# atmega16u2custom2.net
KiCad netlist of a schematic drawn in EAGLE
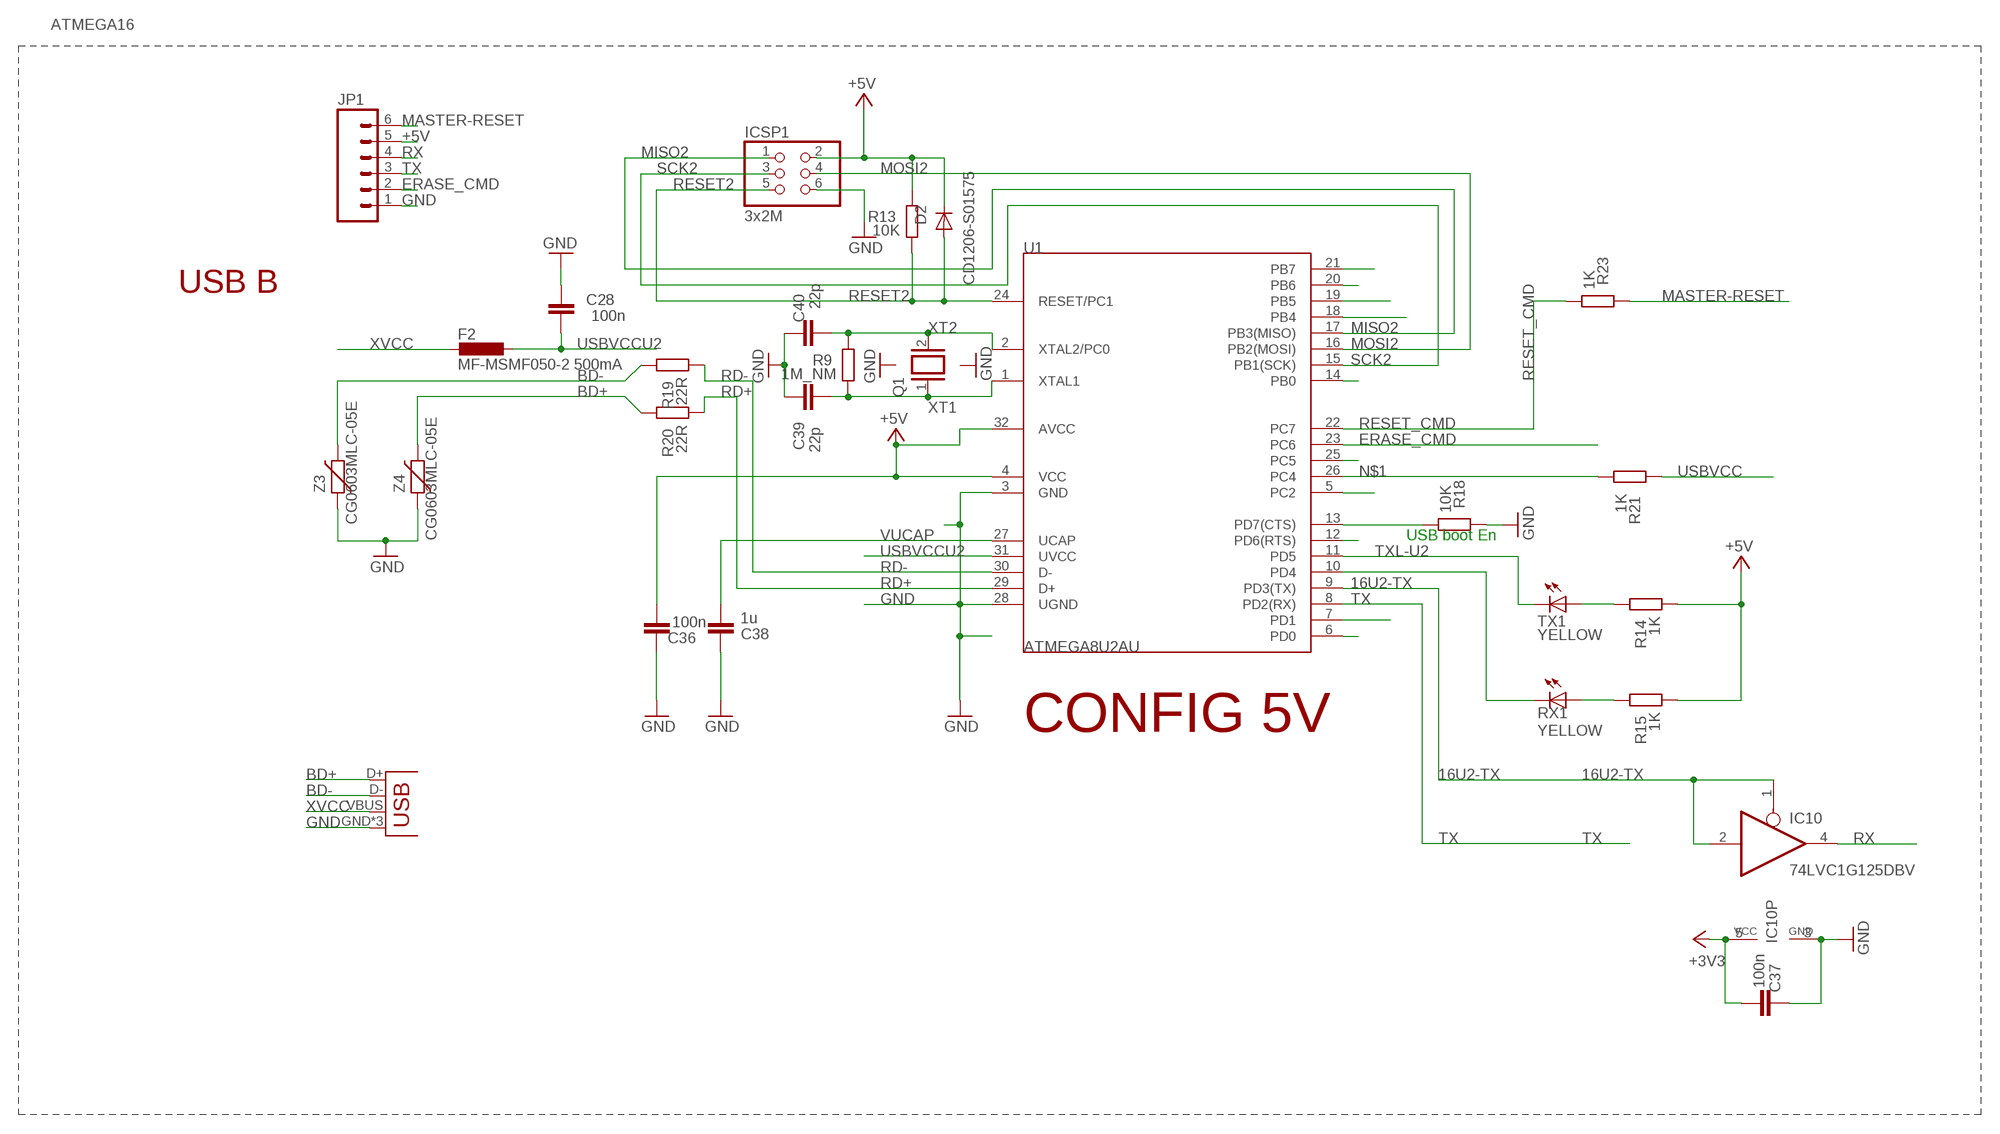
[diagram p0: schematic, sheet 1]

(export (version "E")
  (design (tool "Eeschema 10.0.6"))
  (components
    (comp (ref "C28")
      (value "100n")
      (footprint "eagle-import:C0805")
      (libsource (lib "eagle-import") (part "C-EUC0805"))
    )
    (comp (ref "C36")
      (value "100n")
      (footprint "eagle-import:C0805")
      (libsource (lib "eagle-import") (part "C-EUC0805"))
    )
    (comp (ref "C37")
      (value "100n")
      (footprint "eagle-import:C0805")
      (libsource (lib "eagle-import") (part "C-EUC0805"))
    )
    (comp (ref "C38")
      (value "1u")
      (footprint "eagle-import:C0805")
      (libsource (lib "eagle-import") (part "C-EUC0805"))
    )
    (comp (ref "C39")
      (value "22p")
      (footprint "eagle-import:C0805")
      (libsource (lib "eagle-import") (part "C-EUC0805"))
    )
    (comp (ref "C40")
      (value "22p")
      (footprint "eagle-import:C0805")
      (libsource (lib "eagle-import") (part "C-EUC0805"))
    )
    (comp (ref "D2")
      (value "CD1206-S01575")
      (footprint "eagle-import:MINIMELF")
      (libsource (lib "eagle-import") (part "DIODE-MINIMELF"))
    )
    (comp (ref "F2")
      (value "MF-MSMF050-2 500mA")
      (footprint "eagle-import:L1812")
      (libsource (lib "eagle-import") (part "L-EUL1812"))
    )
    (comp (ref "IC10")
      (value "74LVC1G125DBV")
      (footprint "eagle-import:SOT23-5")
      (libsource (lib "eagle-import") (part "741G125DBVLVC"))
    )
    (comp (ref "ICSP1")
      (value "3x2M")
      (footprint "eagle-import:2X03")
      (libsource (lib "eagle-import") (part "PINHD-2X3"))
    )
    (comp (ref "JP1")
      (value "M06NO_SILK")
      (footprint "eagle-import:1X06_NO_SILK")
      (libsource (lib "eagle-import") (part "M06NO_SILK"))
    )
    (comp (ref "JP2")
      (value "USB-MICROB")
      (footprint "eagle-import:USB-MICROB")
      (libsource (lib "eagle-import") (part "USB-MICROB"))
    )
    (comp (ref "Q1")
      (value "XTAL/S")
      (footprint "eagle-import:QS")
      (libsource (lib "eagle-import") (part "XTAL/S"))
    )
    (comp (ref "R9")
      (value "1M_NM")
      (footprint "eagle-import:R0805")
      (libsource (lib "eagle-import") (part "R-EU_R0805"))
    )
    (comp (ref "R13")
      (value "10K")
      (footprint "eagle-import:R0805")
      (libsource (lib "eagle-import") (part "R-EU_R0805"))
    )
    (comp (ref "R14")
      (value "1K")
      (footprint "eagle-import:R0805")
      (libsource (lib "eagle-import") (part "R-EU_R0805"))
    )
    (comp (ref "R15")
      (value "1K")
      (footprint "eagle-import:R0805")
      (libsource (lib "eagle-import") (part "R-EU_R0805"))
    )
    (comp (ref "R18")
      (value "10K")
      (footprint "eagle-import:R0805")
      (libsource (lib "eagle-import") (part "R-EU_R0805"))
    )
    (comp (ref "R19")
      (value "22R")
      (footprint "eagle-import:R0805")
      (libsource (lib "eagle-import") (part "R-EU_R0805"))
    )
    (comp (ref "R20")
      (value "22R")
      (footprint "eagle-import:R0805")
      (libsource (lib "eagle-import") (part "R-EU_R0805"))
    )
    (comp (ref "R21")
      (value "1K")
      (footprint "eagle-import:R0805")
      (libsource (lib "eagle-import") (part "R-EU_R0805"))
    )
    (comp (ref "R23")
      (value "1K")
      (footprint "eagle-import:R0805")
      (libsource (lib "eagle-import") (part "R-EU_R0805"))
    )
    (comp (ref "RX1")
      (value "YELLOW")
      (footprint "eagle-import:CHIP-LED0805")
      (libsource (lib "eagle-import") (part "LEDCHIP-LED0805"))
    )
    (comp (ref "TX1")
      (value "YELLOW")
      (footprint "eagle-import:CHIP-LED0805")
      (libsource (lib "eagle-import") (part "LEDCHIP-LED0805"))
    )
    (comp (ref "U1")
      (value "ATMEGA8U2AU")
      (footprint "eagle-import:TQFP32-08")
      (libsource (lib "eagle-import") (part "ATMEGA8U2AU"))
    )
    (comp (ref "Z3")
      (value "CG0603MLC-05E")
      (footprint "eagle-import:CT_CN0603")
      (libsource (lib "eagle-import") (part "VARISTORCN0603"))
    )
    (comp (ref "Z4")
      (value "CG0603MLC-05E")
      (footprint "eagle-import:CT_CN0603")
      (libsource (lib "eagle-import") (part "VARISTORCN0603"))
    )
  )
  (nets
    (net (code "1") (name "+3V3") (class "Default")
      (node (ref "C37") (pin "1") (pinfunction "1_1") (pintype "passive"))
      (node (ref "IC10") (pin "5") (pinfunction "VCC_5") (pintype "power_in"))
    )
    (net (code "2") (name "+5V") (class "Default")
      (node (ref "C36") (pin "1") (pinfunction "1_1") (pintype "passive"))
      (node (ref "D2") (pin "C") (pinfunction "C_C") (pintype "passive"))
      (node (ref "ICSP1") (pin "2") (pinfunction "2_2") (pintype "passive"))
      (node (ref "JP1") (pin "5") (pinfunction "5_5") (pintype "passive"))
      (node (ref "R13") (pin "2") (pinfunction "2_2") (pintype "passive"))
      (node (ref "R14") (pin "1") (pinfunction "1_1") (pintype "passive"))
      (node (ref "R15") (pin "1") (pinfunction "1_1") (pintype "passive"))
      (node (ref "U1") (pin "32") (pinfunction "AVCC_32") (pintype "bidirectional"))
      (node (ref "U1") (pin "4") (pinfunction "VCC_4") (pintype "bidirectional"))
    )
    (net (code "3") (name "/16U2-TX") (class "Default")
      (node (ref "IC10") (pin "1") (pinfunction "OE_1") (pintype "input"))
      (node (ref "IC10") (pin "2") (pinfunction "I_2") (pintype "input"))
      (node (ref "U1") (pin "9") (pinfunction "PD3(TX)_9") (pintype "bidirectional"))
    )
    (net (code "4") (name "/BD+") (class "Default")
      (node (ref "JP2") (pin "D+") (pinfunction "D+_D+") (pintype "bidirectional"))
      (node (ref "R20") (pin "2") (pinfunction "2_2") (pintype "passive"))
      (node (ref "Z4") (pin "2") (pinfunction "2_2") (pintype "passive"))
    )
    (net (code "5") (name "/BD-") (class "Default")
      (node (ref "JP2") (pin "D-") (pinfunction "D-_D-") (pintype "bidirectional"))
      (node (ref "R19") (pin "2") (pinfunction "2_2") (pintype "passive"))
      (node (ref "Z3") (pin "2") (pinfunction "2_2") (pintype "passive"))
    )
    (net (code "6") (name "/ERASE_CMD") (class "Default")
      (node (ref "JP1") (pin "2") (pinfunction "2_2") (pintype "passive"))
      (node (ref "U1") (pin "23") (pinfunction "PC6_23") (pintype "bidirectional"))
    )
    (net (code "7") (name "/MASTER-RESET") (class "Default")
      (node (ref "JP1") (pin "6") (pinfunction "6_6") (pintype "passive"))
      (node (ref "R23") (pin "2") (pinfunction "2_2") (pintype "passive"))
    )
    (net (code "8") (name "/MISO2") (class "Default")
      (node (ref "ICSP1") (pin "1") (pinfunction "1_1") (pintype "passive"))
      (node (ref "U1") (pin "17") (pinfunction "PB3(MISO)_17") (pintype "bidirectional"))
    )
    (net (code "9") (name "/MOSI2") (class "Default")
      (node (ref "ICSP1") (pin "4") (pinfunction "4_4") (pintype "passive"))
      (node (ref "U1") (pin "16") (pinfunction "PB2(MOSI)_16") (pintype "bidirectional"))
    )
    (net (code "10") (name "/N$1") (class "Default")
      (node (ref "R21") (pin "1") (pinfunction "1_1") (pintype "passive"))
      (node (ref "U1") (pin "26") (pinfunction "PC4_26") (pintype "bidirectional"))
    )
    (net (code "11") (name "/RD+") (class "Default")
      (node (ref "R20") (pin "1") (pinfunction "1_1") (pintype "passive"))
      (node (ref "U1") (pin "29") (pinfunction "D+_29") (pintype "bidirectional"))
    )
    (net (code "12") (name "/RD-") (class "Default")
      (node (ref "R19") (pin "1") (pinfunction "1_1") (pintype "passive"))
      (node (ref "U1") (pin "30") (pinfunction "D-_30") (pintype "bidirectional"))
    )
    (net (code "13") (name "/RESET2") (class "Default")
      (node (ref "D2") (pin "A") (pinfunction "A_A") (pintype "passive"))
      (node (ref "ICSP1") (pin "5") (pinfunction "5_5") (pintype "passive"))
      (node (ref "R13") (pin "1") (pinfunction "1_1") (pintype "passive"))
      (node (ref "U1") (pin "24") (pinfunction "RESET/PC1_24") (pintype "bidirectional"))
    )
    (net (code "14") (name "/RESET_CMD") (class "Default")
      (node (ref "R23") (pin "1") (pinfunction "1_1") (pintype "passive"))
      (node (ref "U1") (pin "22") (pinfunction "PC7_22") (pintype "bidirectional"))
    )
    (net (code "15") (name "/RX") (class "Default")
      (node (ref "IC10") (pin "4") (pinfunction "O_4") (pintype "tri_state"))
      (node (ref "JP1") (pin "4") (pinfunction "4_4") (pintype "passive"))
    )
    (net (code "16") (name "/SCK2") (class "Default")
      (node (ref "ICSP1") (pin "3") (pinfunction "3_3") (pintype "passive"))
      (node (ref "U1") (pin "15") (pinfunction "PB1(SCK)_15") (pintype "bidirectional"))
    )
    (net (code "17") (name "/TX") (class "Default")
      (node (ref "JP1") (pin "3") (pinfunction "3_3") (pintype "passive"))
      (node (ref "U1") (pin "8") (pinfunction "PD2(RX)_8") (pintype "bidirectional"))
    )
    (net (code "18") (name "/TXL-U2") (class "Default")
      (node (ref "TX1") (pin "C") (pinfunction "C_C") (pintype "passive"))
      (node (ref "U1") (pin "11") (pinfunction "PD5_11") (pintype "bidirectional"))
    )
    (net (code "19") (name "/USBVCC") (class "Default")
      (node (ref "R21") (pin "2") (pinfunction "2_2") (pintype "passive"))
    )
    (net (code "20") (name "/USBVCCU2") (class "Default")
      (node (ref "C28") (pin "1") (pinfunction "1_1") (pintype "passive"))
      (node (ref "F2") (pin "1") (pinfunction "1_1") (pintype "passive"))
      (node (ref "U1") (pin "31") (pinfunction "UVCC_31") (pintype "bidirectional"))
    )
    (net (code "21") (name "/VUCAP") (class "Default")
      (node (ref "C38") (pin "1") (pinfunction "1_1") (pintype "passive"))
      (node (ref "U1") (pin "27") (pinfunction "UCAP_27") (pintype "bidirectional"))
    )
    (net (code "22") (name "/XT1") (class "Default")
      (node (ref "C39") (pin "1") (pinfunction "1_1") (pintype "passive"))
      (node (ref "Q1") (pin "1") (pinfunction "1_1") (pintype "passive"))
      (node (ref "R9") (pin "1") (pinfunction "1_1") (pintype "passive"))
      (node (ref "U1") (pin "1") (pinfunction "XTAL1_1") (pintype "bidirectional"))
    )
    (net (code "23") (name "/XT2") (class "Default")
      (node (ref "C40") (pin "1") (pinfunction "1_1") (pintype "passive"))
      (node (ref "Q1") (pin "2") (pinfunction "2_2") (pintype "passive"))
      (node (ref "R9") (pin "2") (pinfunction "2_2") (pintype "passive"))
      (node (ref "U1") (pin "2") (pinfunction "XTAL2/PC0_2") (pintype "bidirectional"))
    )
    (net (code "24") (name "/XVCC") (class "Default")
      (node (ref "F2") (pin "2") (pinfunction "2_2") (pintype "passive"))
      (node (ref "JP2") (pin "VBUS") (pinfunction "VBUS_VBUS") (pintype "bidirectional"))
    )
    (net (code "25") (name "GND") (class "Default")
      (node (ref "C28") (pin "2") (pinfunction "2_2") (pintype "passive"))
      (node (ref "C36") (pin "2") (pinfunction "2_2") (pintype "passive"))
      (node (ref "C37") (pin "2") (pinfunction "2_2") (pintype "passive"))
      (node (ref "C38") (pin "2") (pinfunction "2_2") (pintype "passive"))
      (node (ref "C39") (pin "2") (pinfunction "2_2") (pintype "passive"))
      (node (ref "C40") (pin "2") (pinfunction "2_2") (pintype "passive"))
      (node (ref "IC10") (pin "3") (pinfunction "GND_3") (pintype "power_in"))
      (node (ref "ICSP1") (pin "6") (pinfunction "6_6") (pintype "passive"))
      (node (ref "JP1") (pin "1") (pinfunction "1_1") (pintype "passive"))
      (node (ref "JP2") (pin "GND") (pinfunction "GND_GND") (pintype "bidirectional"))
      (node (ref "JP2") (pin "MT1") (pinfunction "GND_MT1") (pintype "bidirectional"))
      (node (ref "JP2") (pin "MT2") (pinfunction "GND_MT2") (pintype "bidirectional"))
      (node (ref "R18") (pin "2") (pinfunction "2_2") (pintype "passive"))
      (node (ref "U1") (pin "28") (pinfunction "UGND_28") (pintype "bidirectional"))
      (node (ref "U1") (pin "3") (pinfunction "GND_3") (pintype "bidirectional"))
      (node (ref "Z3") (pin "1") (pinfunction "1_1") (pintype "passive"))
      (node (ref "Z4") (pin "1") (pinfunction "1_1") (pintype "passive"))
    )
    (net (code "26") (name "Net-(R14-Pad2)") (class "Default")
      (node (ref "R14") (pin "2") (pinfunction "2_2") (pintype "passive"))
      (node (ref "TX1") (pin "A") (pinfunction "A_A") (pintype "passive"))
    )
    (net (code "27") (name "Net-(R15-Pad2)") (class "Default")
      (node (ref "R15") (pin "2") (pinfunction "2_2") (pintype "passive"))
      (node (ref "RX1") (pin "A") (pinfunction "A_A") (pintype "passive"))
    )
    (net (code "28") (name "Net-(U1-PD4)") (class "Default")
      (node (ref "RX1") (pin "C") (pinfunction "C_C") (pintype "passive"))
      (node (ref "U1") (pin "10") (pinfunction "PD4_10") (pintype "bidirectional"))
    )
    (net (code "29") (name "Net-(U1-PD7(CTS))") (class "Default")
      (node (ref "R18") (pin "1") (pinfunction "1_1") (pintype "passive"))
      (node (ref "U1") (pin "13") (pinfunction "PD7(CTS)_13") (pintype "bidirectional"))
    )
    (net (code "30") (name "unconnected-(U1-PB0-Pad14)") (class "Default")
      (node (ref "U1") (pin "14") (pinfunction "PB0_14") (pintype "bidirectional"))
    )
    (net (code "31") (name "unconnected-(U1-PB4-Pad18)") (class "Default")
      (node (ref "U1") (pin "18") (pinfunction "PB4_18") (pintype "bidirectional"))
    )
    (net (code "32") (name "unconnected-(U1-PB5-Pad19)") (class "Default")
      (node (ref "U1") (pin "19") (pinfunction "PB5_19") (pintype "bidirectional"))
    )
    (net (code "33") (name "unconnected-(U1-PB6-Pad20)") (class "Default")
      (node (ref "U1") (pin "20") (pinfunction "PB6_20") (pintype "bidirectional"))
    )
    (net (code "34") (name "unconnected-(U1-PB7-Pad21)") (class "Default")
      (node (ref "U1") (pin "21") (pinfunction "PB7_21") (pintype "bidirectional"))
    )
    (net (code "35") (name "unconnected-(U1-PC2-Pad5)") (class "Default")
      (node (ref "U1") (pin "5") (pinfunction "PC2_5") (pintype "bidirectional"))
    )
    (net (code "36") (name "unconnected-(U1-PC5-Pad25)") (class "Default")
      (node (ref "U1") (pin "25") (pinfunction "PC5_25") (pintype "bidirectional"))
    )
    (net (code "37") (name "unconnected-(U1-PD0-Pad6)") (class "Default")
      (node (ref "U1") (pin "6") (pinfunction "PD0_6") (pintype "bidirectional"))
    )
    (net (code "38") (name "unconnected-(U1-PD1-Pad7)") (class "Default")
      (node (ref "U1") (pin "7") (pinfunction "PD1_7") (pintype "bidirectional"))
    )
    (net (code "39") (name "unconnected-(U1-PD6(RTS)-Pad12)") (class "Default")
      (node (ref "U1") (pin "12") (pinfunction "PD6(RTS)_12") (pintype "bidirectional"))
    )
  )
)
